# secondary_decoupling.net
KiCad netlist of a schematic drawn in Altium Designer
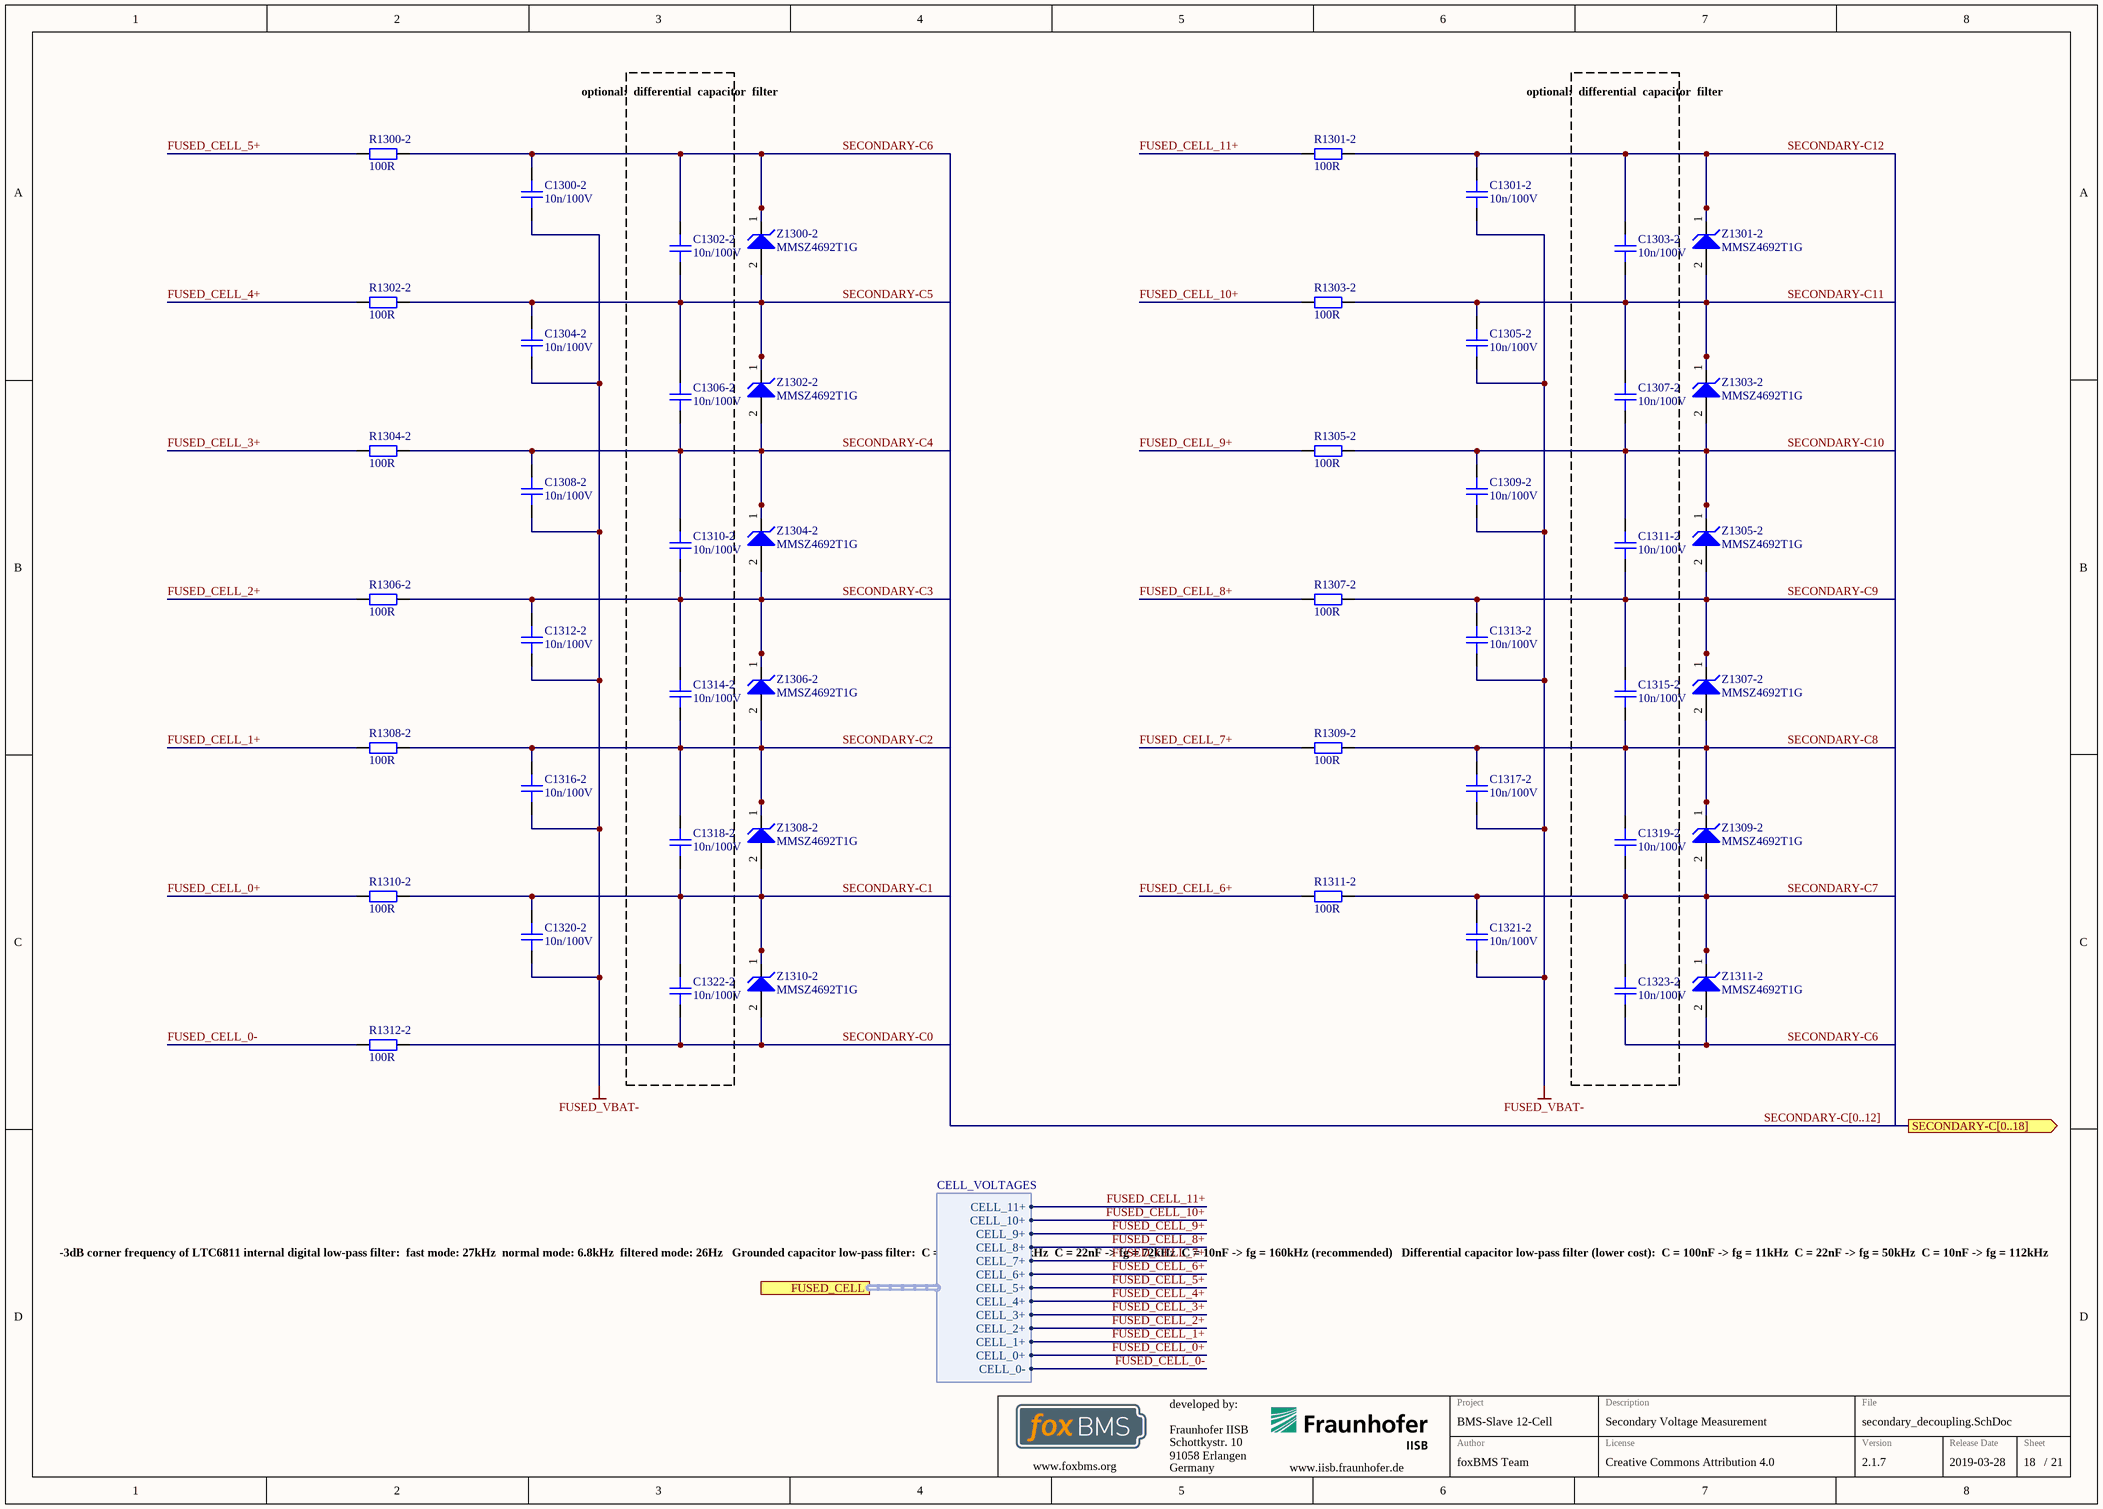
[diagram p0: secondary_decoupling.SchDoc]

(export (version "E")
  (design (tool "Eeschema 10.0.6"))
  (components
    (comp (ref "C1300-2")
      (value "10n/100V")
      (footprint "CAPC1608X08N")
      (description "MLCC")
      (fields (field (name "PART NUMBER") "gen_C_ceramic_10n_100V_X7R_0603"))
      (libsource (lib "OE750") (part "C"))
    )
    (comp (ref "C1301-2")
      (value "10n/100V")
      (footprint "CAPC1608X08N")
      (description "MLCC")
      (fields (field (name "PART NUMBER") "gen_C_ceramic_10n_100V_X7R_0603"))
      (libsource (lib "OE750") (part "C"))
    )
    (comp (ref "C1302-2")
      (value "10n/100V")
      (footprint "CAPC1608X08N")
      (description "MLCC")
      (fields (field (name "PART NUMBER") "gen_C_ceramic_10n_100V_X7R_0603"))
      (libsource (lib "OE750") (part "C"))
    )
    (comp (ref "C1303-2")
      (value "10n/100V")
      (footprint "CAPC1608X08N")
      (description "MLCC")
      (fields (field (name "PART NUMBER") "gen_C_ceramic_10n_100V_X7R_0603"))
      (libsource (lib "OE750") (part "C"))
    )
    (comp (ref "C1304-2")
      (value "10n/100V")
      (footprint "CAPC1608X08N")
      (description "MLCC")
      (fields (field (name "PART NUMBER") "gen_C_ceramic_10n_100V_X7R_0603"))
      (libsource (lib "OE750") (part "C"))
    )
    (comp (ref "C1305-2")
      (value "10n/100V")
      (footprint "CAPC1608X08N")
      (description "MLCC")
      (fields (field (name "PART NUMBER") "gen_C_ceramic_10n_100V_X7R_0603"))
      (libsource (lib "OE750") (part "C"))
    )
    (comp (ref "C1306-2")
      (value "10n/100V")
      (footprint "CAPC1608X08N")
      (description "MLCC")
      (fields (field (name "PART NUMBER") "gen_C_ceramic_10n_100V_X7R_0603"))
      (libsource (lib "OE750") (part "C"))
    )
    (comp (ref "C1307-2")
      (value "10n/100V")
      (footprint "CAPC1608X08N")
      (description "MLCC")
      (fields (field (name "PART NUMBER") "gen_C_ceramic_10n_100V_X7R_0603"))
      (libsource (lib "OE750") (part "C"))
    )
    (comp (ref "C1308-2")
      (value "10n/100V")
      (footprint "CAPC1608X08N")
      (description "MLCC")
      (fields (field (name "PART NUMBER") "gen_C_ceramic_10n_100V_X7R_0603"))
      (libsource (lib "OE750") (part "C"))
    )
    (comp (ref "C1309-2")
      (value "10n/100V")
      (footprint "CAPC1608X08N")
      (description "MLCC")
      (fields (field (name "PART NUMBER") "gen_C_ceramic_10n_100V_X7R_0603"))
      (libsource (lib "OE750") (part "C"))
    )
    (comp (ref "C1310-2")
      (value "10n/100V")
      (footprint "CAPC1608X08N")
      (description "MLCC")
      (fields (field (name "PART NUMBER") "gen_C_ceramic_10n_100V_X7R_0603"))
      (libsource (lib "OE750") (part "C"))
    )
    (comp (ref "C1311-2")
      (value "10n/100V")
      (footprint "CAPC1608X08N")
      (description "MLCC")
      (fields (field (name "PART NUMBER") "gen_C_ceramic_10n_100V_X7R_0603"))
      (libsource (lib "OE750") (part "C"))
    )
    (comp (ref "C1312-2")
      (value "10n/100V")
      (footprint "CAPC1608X08N")
      (description "MLCC")
      (fields (field (name "PART NUMBER") "gen_C_ceramic_10n_100V_X7R_0603"))
      (libsource (lib "OE750") (part "C"))
    )
    (comp (ref "C1313-2")
      (value "10n/100V")
      (footprint "CAPC1608X08N")
      (description "MLCC")
      (fields (field (name "PART NUMBER") "gen_C_ceramic_10n_100V_X7R_0603"))
      (libsource (lib "OE750") (part "C"))
    )
    (comp (ref "C1314-2")
      (value "10n/100V")
      (footprint "CAPC1608X08N")
      (description "MLCC")
      (fields (field (name "PART NUMBER") "gen_C_ceramic_10n_100V_X7R_0603"))
      (libsource (lib "OE750") (part "C"))
    )
    (comp (ref "C1315-2")
      (value "10n/100V")
      (footprint "CAPC1608X08N")
      (description "MLCC")
      (fields (field (name "PART NUMBER") "gen_C_ceramic_10n_100V_X7R_0603"))
      (libsource (lib "OE750") (part "C"))
    )
    (comp (ref "C1316-2")
      (value "10n/100V")
      (footprint "CAPC1608X08N")
      (description "MLCC")
      (fields (field (name "PART NUMBER") "gen_C_ceramic_10n_100V_X7R_0603"))
      (libsource (lib "OE750") (part "C"))
    )
    (comp (ref "C1317-2")
      (value "10n/100V")
      (footprint "CAPC1608X08N")
      (description "MLCC")
      (fields (field (name "PART NUMBER") "gen_C_ceramic_10n_100V_X7R_0603"))
      (libsource (lib "OE750") (part "C"))
    )
    (comp (ref "C1318-2")
      (value "10n/100V")
      (footprint "CAPC1608X08N")
      (description "MLCC")
      (fields (field (name "PART NUMBER") "gen_C_ceramic_10n_100V_X7R_0603"))
      (libsource (lib "OE750") (part "C"))
    )
    (comp (ref "C1319-2")
      (value "10n/100V")
      (footprint "CAPC1608X08N")
      (description "MLCC")
      (fields (field (name "PART NUMBER") "gen_C_ceramic_10n_100V_X7R_0603"))
      (libsource (lib "OE750") (part "C"))
    )
    (comp (ref "C1320-2")
      (value "10n/100V")
      (footprint "CAPC1608X08N")
      (description "MLCC")
      (fields (field (name "PART NUMBER") "gen_C_ceramic_10n_100V_X7R_0603"))
      (libsource (lib "OE750") (part "C"))
    )
    (comp (ref "C1321-2")
      (value "10n/100V")
      (footprint "CAPC1608X08N")
      (description "MLCC")
      (fields (field (name "PART NUMBER") "gen_C_ceramic_10n_100V_X7R_0603"))
      (libsource (lib "OE750") (part "C"))
    )
    (comp (ref "C1322-2")
      (value "10n/100V")
      (footprint "CAPC1608X08N")
      (description "MLCC")
      (fields (field (name "PART NUMBER") "gen_C_ceramic_10n_100V_X7R_0603"))
      (libsource (lib "OE750") (part "C"))
    )
    (comp (ref "C1323-2")
      (value "10n/100V")
      (footprint "CAPC1608X08N")
      (description "MLCC")
      (fields (field (name "PART NUMBER") "gen_C_ceramic_10n_100V_X7R_0603"))
      (libsource (lib "OE750") (part "C"))
    )
    (comp (ref "R1300-2")
      (value "100R")
      (footprint "RESC1608X05N")
      (description "SMD Resistor 100R 0603")
      (fields (field (name "PART NUMBER") "gen_R_100R_0603") (field (name "TOLERANCE") "1%"))
      (libsource (lib "OE750") (part "R"))
    )
    (comp (ref "R1301-2")
      (value "100R")
      (footprint "RESC1608X05N")
      (description "SMD Resistor 100R 0603")
      (fields (field (name "PART NUMBER") "gen_R_100R_0603") (field (name "TOLERANCE") "1%"))
      (libsource (lib "OE750") (part "R"))
    )
    (comp (ref "R1302-2")
      (value "100R")
      (footprint "RESC1608X05N")
      (description "SMD Resistor 100R 0603")
      (fields (field (name "PART NUMBER") "gen_R_100R_0603") (field (name "TOLERANCE") "1%"))
      (libsource (lib "OE750") (part "R"))
    )
    (comp (ref "R1303-2")
      (value "100R")
      (footprint "RESC1608X05N")
      (description "SMD Resistor 100R 0603")
      (fields (field (name "PART NUMBER") "gen_R_100R_0603") (field (name "TOLERANCE") "1%"))
      (libsource (lib "OE750") (part "R"))
    )
    (comp (ref "R1304-2")
      (value "100R")
      (footprint "RESC1608X05N")
      (description "SMD Resistor 100R 0603")
      (fields (field (name "PART NUMBER") "gen_R_100R_0603") (field (name "TOLERANCE") "1%"))
      (libsource (lib "OE750") (part "R"))
    )
    (comp (ref "R1305-2")
      (value "100R")
      (footprint "RESC1608X05N")
      (description "SMD Resistor 100R 0603")
      (fields (field (name "PART NUMBER") "gen_R_100R_0603") (field (name "TOLERANCE") "1%"))
      (libsource (lib "OE750") (part "R"))
    )
    (comp (ref "R1306-2")
      (value "100R")
      (footprint "RESC1608X05N")
      (description "SMD Resistor 100R 0603")
      (fields (field (name "PART NUMBER") "gen_R_100R_0603") (field (name "TOLERANCE") "1%"))
      (libsource (lib "OE750") (part "R"))
    )
    (comp (ref "R1307-2")
      (value "100R")
      (footprint "RESC1608X05N")
      (description "SMD Resistor 100R 0603")
      (fields (field (name "PART NUMBER") "gen_R_100R_0603") (field (name "TOLERANCE") "1%"))
      (libsource (lib "OE750") (part "R"))
    )
    (comp (ref "R1308-2")
      (value "100R")
      (footprint "RESC1608X05N")
      (description "SMD Resistor 100R 0603")
      (fields (field (name "PART NUMBER") "gen_R_100R_0603") (field (name "TOLERANCE") "1%"))
      (libsource (lib "OE750") (part "R"))
    )
    (comp (ref "R1309-2")
      (value "100R")
      (footprint "RESC1608X05N")
      (description "SMD Resistor 100R 0603")
      (fields (field (name "PART NUMBER") "gen_R_100R_0603") (field (name "TOLERANCE") "1%"))
      (libsource (lib "OE750") (part "R"))
    )
    (comp (ref "R1310-2")
      (value "100R")
      (footprint "RESC1608X05N")
      (description "SMD Resistor 100R 0603")
      (fields (field (name "PART NUMBER") "gen_R_100R_0603") (field (name "TOLERANCE") "1%"))
      (libsource (lib "OE750") (part "R"))
    )
    (comp (ref "R1311-2")
      (value "100R")
      (footprint "RESC1608X05N")
      (description "SMD Resistor 100R 0603")
      (fields (field (name "PART NUMBER") "gen_R_100R_0603") (field (name "TOLERANCE") "1%"))
      (libsource (lib "OE750") (part "R"))
    )
    (comp (ref "R1312-2")
      (value "100R")
      (footprint "RESC1608X05N")
      (description "SMD Resistor 100R 0603")
      (fields (field (name "PART NUMBER") "gen_R_100R_0603") (field (name "TOLERANCE") "1%"))
      (libsource (lib "OE750") (part "R"))
    )
    (comp (ref "Z1300-2")
      (value "MMSZ4692T1G")
      (footprint "ONSC-SOD-123-2-425-04_V")
      (description "Zener Voltage Regulator, 500 mW, 2-Pin SOD-123, Pb-Free, Tape and Reel")
      (fields (field (name "MANUFACTURER") "On Semiconductor"))
      (libsource (lib "Altium Content Vault") (part "ONSC-K1A2-2"))
    )
    (comp (ref "Z1301-2")
      (value "MMSZ4692T1G")
      (footprint "ONSC-SOD-123-2-425-04_V")
      (description "Zener Voltage Regulator, 500 mW, 2-Pin SOD-123, Pb-Free, Tape and Reel")
      (fields (field (name "MANUFACTURER") "On Semiconductor"))
      (libsource (lib "Altium Content Vault") (part "ONSC-K1A2-2"))
    )
    (comp (ref "Z1302-2")
      (value "MMSZ4692T1G")
      (footprint "ONSC-SOD-123-2-425-04_V")
      (description "Zener Voltage Regulator, 500 mW, 2-Pin SOD-123, Pb-Free, Tape and Reel")
      (fields (field (name "MANUFACTURER") "On Semiconductor"))
      (libsource (lib "Altium Content Vault") (part "ONSC-K1A2-2"))
    )
    (comp (ref "Z1303-2")
      (value "MMSZ4692T1G")
      (footprint "ONSC-SOD-123-2-425-04_V")
      (description "Zener Voltage Regulator, 500 mW, 2-Pin SOD-123, Pb-Free, Tape and Reel")
      (fields (field (name "MANUFACTURER") "On Semiconductor"))
      (libsource (lib "Altium Content Vault") (part "ONSC-K1A2-2"))
    )
    (comp (ref "Z1304-2")
      (value "MMSZ4692T1G")
      (footprint "ONSC-SOD-123-2-425-04_V")
      (description "Zener Voltage Regulator, 500 mW, 2-Pin SOD-123, Pb-Free, Tape and Reel")
      (fields (field (name "MANUFACTURER") "On Semiconductor"))
      (libsource (lib "Altium Content Vault") (part "ONSC-K1A2-2"))
    )
    (comp (ref "Z1305-2")
      (value "MMSZ4692T1G")
      (footprint "ONSC-SOD-123-2-425-04_V")
      (description "Zener Voltage Regulator, 500 mW, 2-Pin SOD-123, Pb-Free, Tape and Reel")
      (fields (field (name "MANUFACTURER") "On Semiconductor"))
      (libsource (lib "Altium Content Vault") (part "ONSC-K1A2-2"))
    )
    (comp (ref "Z1306-2")
      (value "MMSZ4692T1G")
      (footprint "ONSC-SOD-123-2-425-04_V")
      (description "Zener Voltage Regulator, 500 mW, 2-Pin SOD-123, Pb-Free, Tape and Reel")
      (fields (field (name "MANUFACTURER") "On Semiconductor"))
      (libsource (lib "Altium Content Vault") (part "ONSC-K1A2-2"))
    )
    (comp (ref "Z1307-2")
      (value "MMSZ4692T1G")
      (footprint "ONSC-SOD-123-2-425-04_V")
      (description "Zener Voltage Regulator, 500 mW, 2-Pin SOD-123, Pb-Free, Tape and Reel")
      (fields (field (name "MANUFACTURER") "On Semiconductor"))
      (libsource (lib "Altium Content Vault") (part "ONSC-K1A2-2"))
    )
    (comp (ref "Z1308-2")
      (value "MMSZ4692T1G")
      (footprint "ONSC-SOD-123-2-425-04_V")
      (description "Zener Voltage Regulator, 500 mW, 2-Pin SOD-123, Pb-Free, Tape and Reel")
      (fields (field (name "MANUFACTURER") "On Semiconductor"))
      (libsource (lib "Altium Content Vault") (part "ONSC-K1A2-2"))
    )
    (comp (ref "Z1309-2")
      (value "MMSZ4692T1G")
      (footprint "ONSC-SOD-123-2-425-04_V")
      (description "Zener Voltage Regulator, 500 mW, 2-Pin SOD-123, Pb-Free, Tape and Reel")
      (fields (field (name "MANUFACTURER") "On Semiconductor"))
      (libsource (lib "Altium Content Vault") (part "ONSC-K1A2-2"))
    )
    (comp (ref "Z1310-2")
      (value "MMSZ4692T1G")
      (footprint "ONSC-SOD-123-2-425-04_V")
      (description "Zener Voltage Regulator, 500 mW, 2-Pin SOD-123, Pb-Free, Tape and Reel")
      (fields (field (name "MANUFACTURER") "On Semiconductor"))
      (libsource (lib "Altium Content Vault") (part "ONSC-K1A2-2"))
    )
    (comp (ref "Z1311-2")
      (value "MMSZ4692T1G")
      (footprint "ONSC-SOD-123-2-425-04_V")
      (description "Zener Voltage Regulator, 500 mW, 2-Pin SOD-123, Pb-Free, Tape and Reel")
      (fields (field (name "MANUFACTURER") "On Semiconductor"))
      (libsource (lib "Altium Content Vault") (part "ONSC-K1A2-2"))
    )
  )
  (nets
    (net (code "2") (name "/FUSED_CELL_0+") (class "Default")
      (node (ref "R1310-2") (pin "1") (pinfunction "1_1") (pintype "passive"))
    )
    (net (code "3") (name "/FUSED_CELL_0-") (class "Default")
      (node (ref "R1312-2") (pin "1") (pinfunction "1_1") (pintype "passive"))
    )
    (net (code "4") (name "/FUSED_CELL_1+") (class "Default")
      (node (ref "R1308-2") (pin "1") (pinfunction "1_1") (pintype "passive"))
    )
    (net (code "5") (name "/FUSED_CELL_2+") (class "Default")
      (node (ref "R1306-2") (pin "1") (pinfunction "1_1") (pintype "passive"))
    )
    (net (code "6") (name "/FUSED_CELL_3+") (class "Default")
      (node (ref "R1304-2") (pin "1") (pinfunction "1_1") (pintype "passive"))
    )
    (net (code "7") (name "/FUSED_CELL_4+") (class "Default")
      (node (ref "R1302-2") (pin "1") (pinfunction "1_1") (pintype "passive"))
    )
    (net (code "8") (name "/FUSED_CELL_5+") (class "Default")
      (node (ref "R1300-2") (pin "1") (pinfunction "1_1") (pintype "passive"))
    )
    (net (code "9") (name "/FUSED_CELL_6+") (class "Default")
      (node (ref "R1311-2") (pin "1") (pinfunction "1_1") (pintype "passive"))
    )
    (net (code "10") (name "/FUSED_CELL_7+") (class "Default")
      (node (ref "R1309-2") (pin "1") (pinfunction "1_1") (pintype "passive"))
    )
    (net (code "11") (name "/FUSED_CELL_8+") (class "Default")
      (node (ref "R1307-2") (pin "1") (pinfunction "1_1") (pintype "passive"))
    )
    (net (code "12") (name "/FUSED_CELL_9+") (class "Default")
      (node (ref "R1305-2") (pin "1") (pinfunction "1_1") (pintype "passive"))
    )
    (net (code "13") (name "/FUSED_CELL_10+") (class "Default")
      (node (ref "R1303-2") (pin "1") (pinfunction "1_1") (pintype "passive"))
    )
    (net (code "14") (name "/FUSED_CELL_11+") (class "Default")
      (node (ref "R1301-2") (pin "1") (pinfunction "1_1") (pintype "passive"))
    )
    (net (code "15") (name "/SECONDARY-C0") (class "Default")
      (node (ref "C1322-2") (pin "2") (pinfunction "2_2") (pintype "passive"))
      (node (ref "R1312-2") (pin "2") (pinfunction "2_2") (pintype "passive"))
      (node (ref "Z1310-2") (pin "2") (pinfunction "A_2") (pintype "passive"))
    )
    (net (code "16") (name "/SECONDARY-C1") (class "Default")
      (node (ref "C1318-2") (pin "2") (pinfunction "2_2") (pintype "passive"))
      (node (ref "C1320-2") (pin "1") (pinfunction "1_1") (pintype "passive"))
      (node (ref "C1322-2") (pin "1") (pinfunction "1_1") (pintype "passive"))
      (node (ref "R1310-2") (pin "2") (pinfunction "2_2") (pintype "passive"))
      (node (ref "Z1308-2") (pin "2") (pinfunction "A_2") (pintype "passive"))
      (node (ref "Z1310-2") (pin "1") (pinfunction "K_1") (pintype "passive"))
    )
    (net (code "17") (name "/SECONDARY-C2") (class "Default")
      (node (ref "C1314-2") (pin "2") (pinfunction "2_2") (pintype "passive"))
      (node (ref "C1316-2") (pin "1") (pinfunction "1_1") (pintype "passive"))
      (node (ref "C1318-2") (pin "1") (pinfunction "1_1") (pintype "passive"))
      (node (ref "R1308-2") (pin "2") (pinfunction "2_2") (pintype "passive"))
      (node (ref "Z1306-2") (pin "2") (pinfunction "A_2") (pintype "passive"))
      (node (ref "Z1308-2") (pin "1") (pinfunction "K_1") (pintype "passive"))
    )
    (net (code "18") (name "/SECONDARY-C3") (class "Default")
      (node (ref "C1310-2") (pin "2") (pinfunction "2_2") (pintype "passive"))
      (node (ref "C1312-2") (pin "1") (pinfunction "1_1") (pintype "passive"))
      (node (ref "C1314-2") (pin "1") (pinfunction "1_1") (pintype "passive"))
      (node (ref "R1306-2") (pin "2") (pinfunction "2_2") (pintype "passive"))
      (node (ref "Z1304-2") (pin "2") (pinfunction "A_2") (pintype "passive"))
      (node (ref "Z1306-2") (pin "1") (pinfunction "K_1") (pintype "passive"))
    )
    (net (code "19") (name "/SECONDARY-C4") (class "Default")
      (node (ref "C1306-2") (pin "2") (pinfunction "2_2") (pintype "passive"))
      (node (ref "C1308-2") (pin "1") (pinfunction "1_1") (pintype "passive"))
      (node (ref "C1310-2") (pin "1") (pinfunction "1_1") (pintype "passive"))
      (node (ref "R1304-2") (pin "2") (pinfunction "2_2") (pintype "passive"))
      (node (ref "Z1302-2") (pin "2") (pinfunction "A_2") (pintype "passive"))
      (node (ref "Z1304-2") (pin "1") (pinfunction "K_1") (pintype "passive"))
    )
    (net (code "20") (name "/SECONDARY-C5") (class "Default")
      (node (ref "C1302-2") (pin "2") (pinfunction "2_2") (pintype "passive"))
      (node (ref "C1304-2") (pin "1") (pinfunction "1_1") (pintype "passive"))
      (node (ref "C1306-2") (pin "1") (pinfunction "1_1") (pintype "passive"))
      (node (ref "R1302-2") (pin "2") (pinfunction "2_2") (pintype "passive"))
      (node (ref "Z1300-2") (pin "2") (pinfunction "A_2") (pintype "passive"))
      (node (ref "Z1302-2") (pin "1") (pinfunction "K_1") (pintype "passive"))
    )
    (net (code "21") (name "/SECONDARY-C6") (class "Default")
      (node (ref "C1300-2") (pin "1") (pinfunction "1_1") (pintype "passive"))
      (node (ref "C1302-2") (pin "1") (pinfunction "1_1") (pintype "passive"))
      (node (ref "C1323-2") (pin "2") (pinfunction "2_2") (pintype "passive"))
      (node (ref "R1300-2") (pin "2") (pinfunction "2_2") (pintype "passive"))
      (node (ref "Z1300-2") (pin "1") (pinfunction "K_1") (pintype "passive"))
      (node (ref "Z1311-2") (pin "2") (pinfunction "A_2") (pintype "passive"))
    )
    (net (code "22") (name "/SECONDARY-C7") (class "Default")
      (node (ref "C1319-2") (pin "2") (pinfunction "2_2") (pintype "passive"))
      (node (ref "C1321-2") (pin "1") (pinfunction "1_1") (pintype "passive"))
      (node (ref "C1323-2") (pin "1") (pinfunction "1_1") (pintype "passive"))
      (node (ref "R1311-2") (pin "2") (pinfunction "2_2") (pintype "passive"))
      (node (ref "Z1309-2") (pin "2") (pinfunction "A_2") (pintype "passive"))
      (node (ref "Z1311-2") (pin "1") (pinfunction "K_1") (pintype "passive"))
    )
    (net (code "23") (name "/SECONDARY-C8") (class "Default")
      (node (ref "C1315-2") (pin "2") (pinfunction "2_2") (pintype "passive"))
      (node (ref "C1317-2") (pin "1") (pinfunction "1_1") (pintype "passive"))
      (node (ref "C1319-2") (pin "1") (pinfunction "1_1") (pintype "passive"))
      (node (ref "R1309-2") (pin "2") (pinfunction "2_2") (pintype "passive"))
      (node (ref "Z1307-2") (pin "2") (pinfunction "A_2") (pintype "passive"))
      (node (ref "Z1309-2") (pin "1") (pinfunction "K_1") (pintype "passive"))
    )
    (net (code "24") (name "/SECONDARY-C9") (class "Default")
      (node (ref "C1311-2") (pin "2") (pinfunction "2_2") (pintype "passive"))
      (node (ref "C1313-2") (pin "1") (pinfunction "1_1") (pintype "passive"))
      (node (ref "C1315-2") (pin "1") (pinfunction "1_1") (pintype "passive"))
      (node (ref "R1307-2") (pin "2") (pinfunction "2_2") (pintype "passive"))
      (node (ref "Z1305-2") (pin "2") (pinfunction "A_2") (pintype "passive"))
      (node (ref "Z1307-2") (pin "1") (pinfunction "K_1") (pintype "passive"))
    )
    (net (code "25") (name "/SECONDARY-C10") (class "Default")
      (node (ref "C1307-2") (pin "2") (pinfunction "2_2") (pintype "passive"))
      (node (ref "C1309-2") (pin "1") (pinfunction "1_1") (pintype "passive"))
      (node (ref "C1311-2") (pin "1") (pinfunction "1_1") (pintype "passive"))
      (node (ref "R1305-2") (pin "2") (pinfunction "2_2") (pintype "passive"))
      (node (ref "Z1303-2") (pin "2") (pinfunction "A_2") (pintype "passive"))
      (node (ref "Z1305-2") (pin "1") (pinfunction "K_1") (pintype "passive"))
    )
    (net (code "26") (name "/SECONDARY-C11") (class "Default")
      (node (ref "C1303-2") (pin "2") (pinfunction "2_2") (pintype "passive"))
      (node (ref "C1305-2") (pin "1") (pinfunction "1_1") (pintype "passive"))
      (node (ref "C1307-2") (pin "1") (pinfunction "1_1") (pintype "passive"))
      (node (ref "R1303-2") (pin "2") (pinfunction "2_2") (pintype "passive"))
      (node (ref "Z1301-2") (pin "2") (pinfunction "A_2") (pintype "passive"))
      (node (ref "Z1303-2") (pin "1") (pinfunction "K_1") (pintype "passive"))
    )
    (net (code "27") (name "/SECONDARY-C12") (class "Default")
      (node (ref "C1301-2") (pin "1") (pinfunction "1_1") (pintype "passive"))
      (node (ref "C1303-2") (pin "1") (pinfunction "1_1") (pintype "passive"))
      (node (ref "R1301-2") (pin "2") (pinfunction "2_2") (pintype "passive"))
      (node (ref "Z1301-2") (pin "1") (pinfunction "K_1") (pintype "passive"))
    )
    (net (code "30") (name "FUSED_VBAT-") (class "Default")
      (node (ref "C1300-2") (pin "2") (pinfunction "2_2") (pintype "passive"))
      (node (ref "C1301-2") (pin "2") (pinfunction "2_2") (pintype "passive"))
      (node (ref "C1304-2") (pin "2") (pinfunction "2_2") (pintype "passive"))
      (node (ref "C1305-2") (pin "2") (pinfunction "2_2") (pintype "passive"))
      (node (ref "C1308-2") (pin "2") (pinfunction "2_2") (pintype "passive"))
      (node (ref "C1309-2") (pin "2") (pinfunction "2_2") (pintype "passive"))
      (node (ref "C1312-2") (pin "2") (pinfunction "2_2") (pintype "passive"))
      (node (ref "C1313-2") (pin "2") (pinfunction "2_2") (pintype "passive"))
      (node (ref "C1316-2") (pin "2") (pinfunction "2_2") (pintype "passive"))
      (node (ref "C1317-2") (pin "2") (pinfunction "2_2") (pintype "passive"))
      (node (ref "C1320-2") (pin "2") (pinfunction "2_2") (pintype "passive"))
      (node (ref "C1321-2") (pin "2") (pinfunction "2_2") (pintype "passive"))
    )
  )
)
